# connectors.net
KiCad netlist of a schematic drawn in Altium Designer
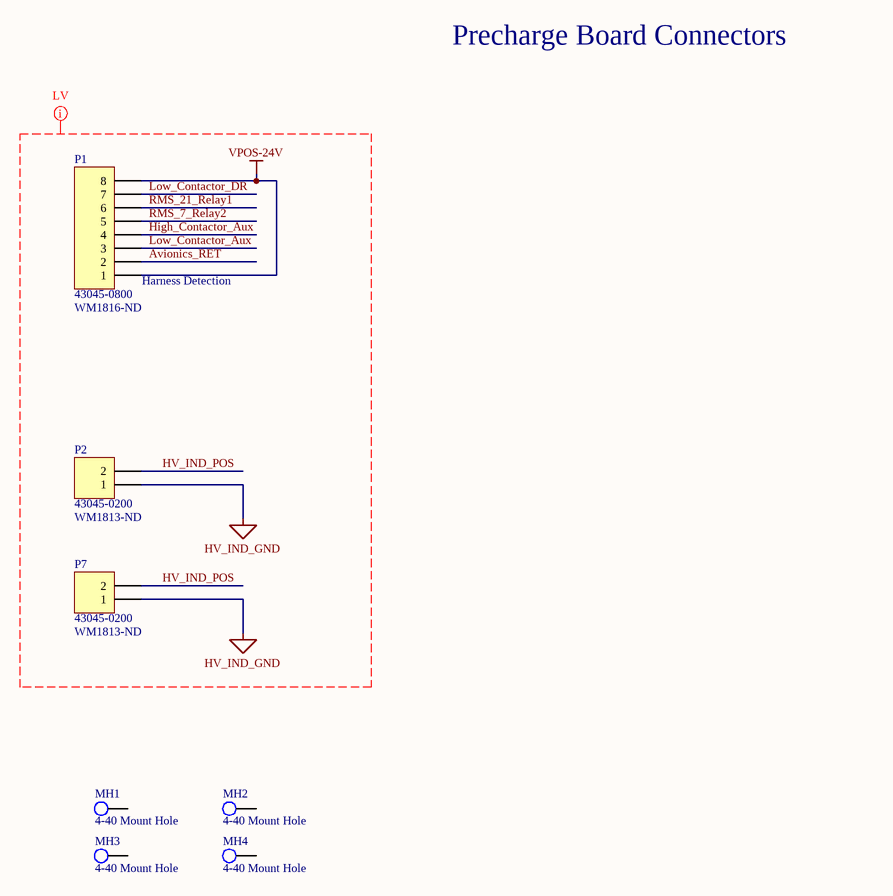
[diagram p0: connectors.SchDoc]

(export (version "E")
  (design (tool "Eeschema 10.0.6"))
  (components
    (comp (ref "MH1")
      (value "4-40 Mount Hole")
      (footprint "MH")
      (libsource (lib "misc") (part "4-40 Mount Hole"))
    )
    (comp (ref "MH2")
      (value "4-40 Mount Hole")
      (footprint "MH")
      (libsource (lib "misc") (part "4-40 Mount Hole"))
    )
    (comp (ref "MH3")
      (value "4-40 Mount Hole")
      (footprint "MH")
      (libsource (lib "misc") (part "4-40 Mount Hole"))
    )
    (comp (ref "MH4")
      (value "4-40 Mount Hole")
      (footprint "MH")
      (libsource (lib "misc") (part "4-40 Mount Hole"))
    )
    (comp (ref "P1")
      (value "43045-0800")
      (footprint "430450800")
      (description "CONN HEADER R/A 8POS 3MM")
      (fields (field (name "MANUFACTURER") "Molex") (field (name "SUPPLIER PART NUMBER 1") "WM1816-ND"))
      (libsource (lib "connector") (part "43045-0800"))
    )
    (comp (ref "P2")
      (value "43045-0200")
      (footprint "430450200")
      (description "CONN HEADER R/A 2POS")
      (fields (field (name "MANUFACTURER") "Molex") (field (name "SUPPLIER PART NUMBER 1") "WM1813-ND"))
      (libsource (lib "connector") (part "43045-0200"))
    )
    (comp (ref "P7")
      (value "43045-0200")
      (footprint "430450200")
      (description "CONN HEADER R/A 2POS")
      (fields (field (name "MANUFACTURER") "Molex") (field (name "SUPPLIER PART NUMBER 1") "WM1813-ND"))
      (libsource (lib "connector") (part "43045-0200"))
    )
  )
  (nets
    (net (code "1") (name "/Avionics_RET") (class "Default")
      (node (ref "P1") (pin "2") (pinfunction "2_2") (pintype "passive"))
    )
    (net (code "2") (name "/HV_IND_POS") (class "Default")
      (node (ref "P2") (pin "2") (pinfunction "2_2") (pintype "passive"))
      (node (ref "P7") (pin "2") (pinfunction "2_2") (pintype "passive"))
    )
    (net (code "3") (name "/High_Contactor_Aux") (class "Default")
      (node (ref "P1") (pin "4") (pinfunction "4_4") (pintype "passive"))
    )
    (net (code "4") (name "/Low_Contactor_Aux") (class "Default")
      (node (ref "P1") (pin "3") (pinfunction "3_3") (pintype "passive"))
    )
    (net (code "5") (name "/Low_Contactor_DR") (class "Default")
      (node (ref "P1") (pin "7") (pinfunction "7_7") (pintype "passive"))
    )
    (net (code "6") (name "/RMS_7_Relay2") (class "Default")
      (node (ref "P1") (pin "5") (pinfunction "5_5") (pintype "passive"))
    )
    (net (code "7") (name "/RMS_21_Relay1") (class "Default")
      (node (ref "P1") (pin "6") (pinfunction "6_6") (pintype "passive"))
    )
    (net (code "8") (name "HV_IND_GND") (class "Default")
      (node (ref "P2") (pin "1") (pinfunction "1_1") (pintype "passive"))
      (node (ref "P7") (pin "1") (pinfunction "1_1") (pintype "passive"))
    )
    (net (code "9") (name "VPOS-24V") (class "Default")
      (node (ref "P1") (pin "1") (pinfunction "1_1") (pintype "passive"))
      (node (ref "P1") (pin "8") (pinfunction "8_8") (pintype "passive"))
    )
    (net (code "10") (name "unconnected-(MH1-Pad46)") (class "Default")
      (node (ref "MH1") (pin "46") (pinfunction "46_46") (pintype "passive"))
    )
    (net (code "11") (name "unconnected-(MH2-Pad46)") (class "Default")
      (node (ref "MH2") (pin "46") (pinfunction "46_46") (pintype "passive"))
    )
    (net (code "12") (name "unconnected-(MH3-Pad46)") (class "Default")
      (node (ref "MH3") (pin "46") (pinfunction "46_46") (pintype "passive"))
    )
    (net (code "13") (name "unconnected-(MH4-Pad46)") (class "Default")
      (node (ref "MH4") (pin "46") (pinfunction "46_46") (pintype "passive"))
    )
  )
)
